# SH4-CONTROLS.net
KiCad netlist of a schematic drawn in Altium Designer
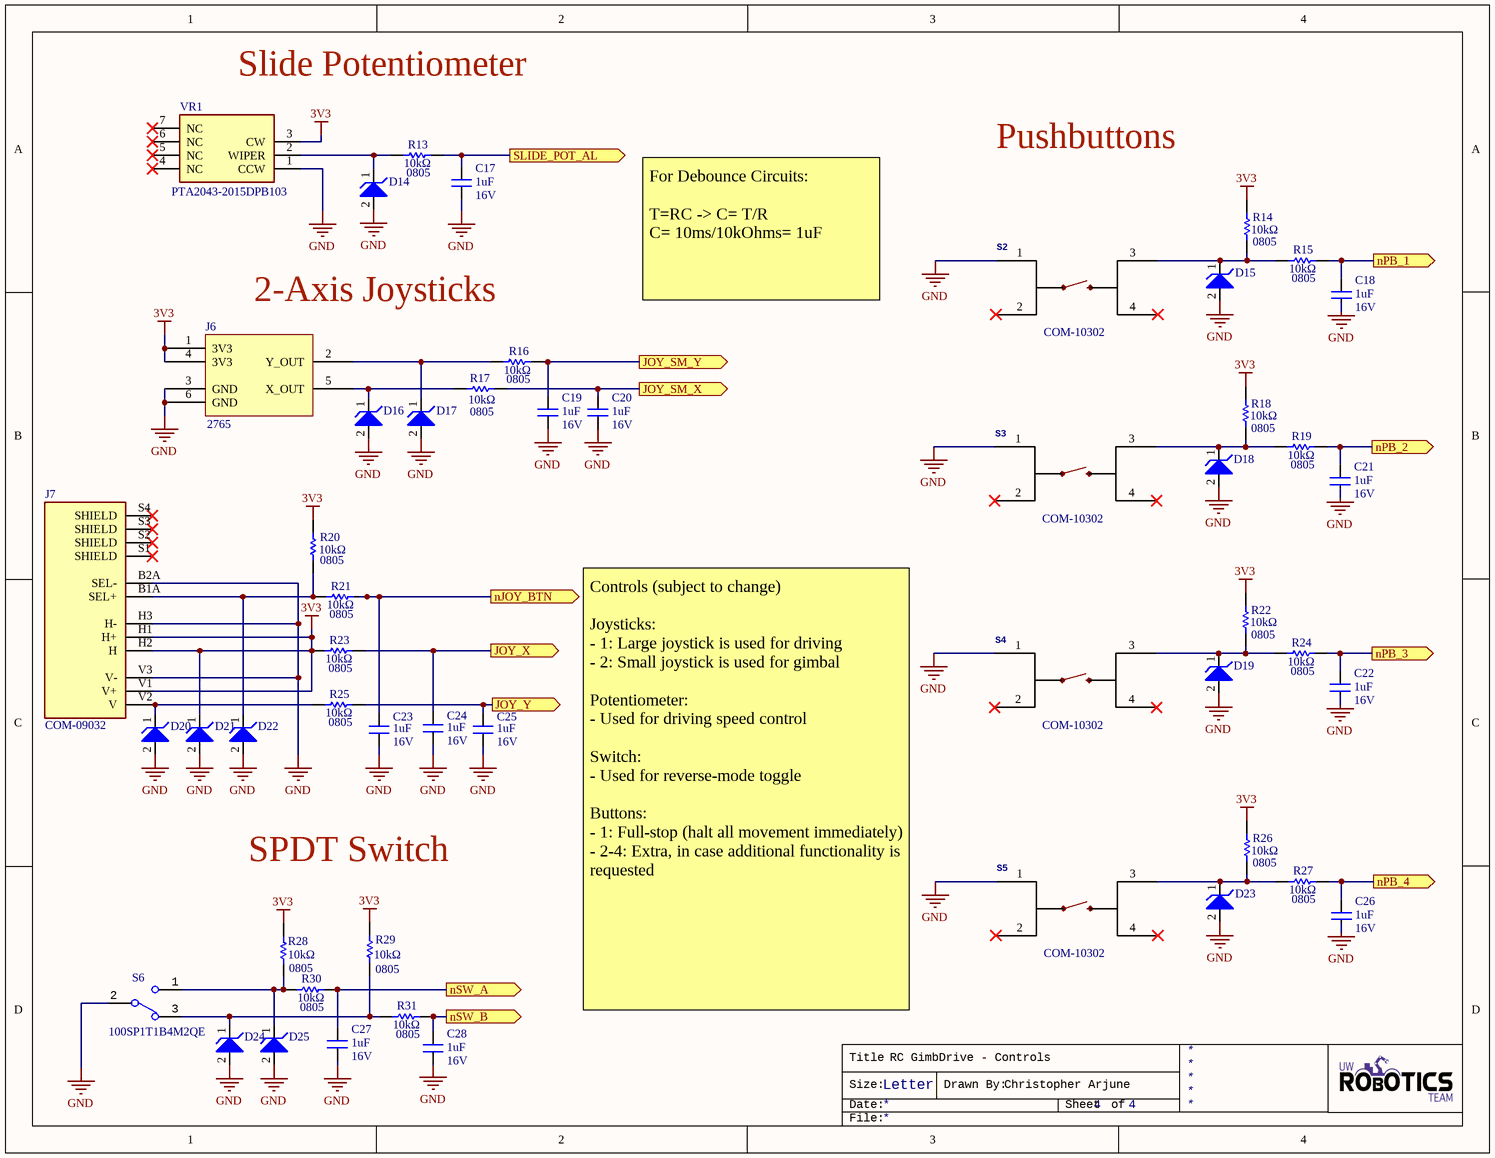
[diagram p0: SH4-CONTROLS.SchDoc]

(export (version "E")
  (design (tool "Eeschema 10.0.6"))
  (components
    (comp (ref "C17")
      (value "1uF")
      (footprint "CAPC2012X140N")
      (description "CAP CER 1UF 16V X7R 0805")
      (fields
        (field (name "TOLERANCE") "10%")
        (field (name "VOLTAGE RATING") "16V")
        (field (name "Comment") "CAP_1uF_16V_0805")
      )
      (libsource (lib "UWRT_Schematic_Library_2020") (part "CAP_1uF_16V_0805"))
    )
    (comp (ref "C18")
      (value "1uF")
      (footprint "CAPC2012X140N")
      (description "CAP CER 1UF 16V X7R 0805")
      (fields
        (field (name "TOLERANCE") "10%")
        (field (name "VOLTAGE RATING") "16V")
        (field (name "Comment") "CAP_1uF_16V_0805")
      )
      (libsource (lib "UWRT_Schematic_Library_2020") (part "CAP_1uF_16V_0805"))
    )
    (comp (ref "C19")
      (value "1uF")
      (footprint "CAPC2012X140N")
      (description "CAP CER 1UF 16V X7R 0805")
      (fields
        (field (name "TOLERANCE") "10%")
        (field (name "VOLTAGE RATING") "16V")
        (field (name "Comment") "CAP_1uF_16V_0805")
      )
      (libsource (lib "UWRT_Schematic_Library_2020") (part "CAP_1uF_16V_0805"))
    )
    (comp (ref "C20")
      (value "1uF")
      (footprint "CAPC2012X140N")
      (description "CAP CER 1UF 16V X7R 0805")
      (fields
        (field (name "TOLERANCE") "10%")
        (field (name "VOLTAGE RATING") "16V")
        (field (name "Comment") "CAP_1uF_16V_0805")
      )
      (libsource (lib "UWRT_Schematic_Library_2020") (part "CAP_1uF_16V_0805"))
    )
    (comp (ref "C21")
      (value "1uF")
      (footprint "CAPC2012X140N")
      (description "CAP CER 1UF 16V X7R 0805")
      (fields
        (field (name "TOLERANCE") "10%")
        (field (name "VOLTAGE RATING") "16V")
        (field (name "Comment") "CAP_1uF_16V_0805")
      )
      (libsource (lib "UWRT_Schematic_Library_2020") (part "CAP_1uF_16V_0805"))
    )
    (comp (ref "C22")
      (value "1uF")
      (footprint "CAPC2012X140N")
      (description "CAP CER 1UF 16V X7R 0805")
      (fields
        (field (name "TOLERANCE") "10%")
        (field (name "VOLTAGE RATING") "16V")
        (field (name "Comment") "CAP_1uF_16V_0805")
      )
      (libsource (lib "UWRT_Schematic_Library_2020") (part "CAP_1uF_16V_0805"))
    )
    (comp (ref "C23")
      (value "1uF")
      (footprint "CAPC2012X140N")
      (description "CAP CER 1UF 16V X7R 0805")
      (fields
        (field (name "TOLERANCE") "10%")
        (field (name "VOLTAGE RATING") "16V")
        (field (name "Comment") "CAP_1uF_16V_0805")
      )
      (libsource (lib "UWRT_Schematic_Library_2020") (part "CAP_1uF_16V_0805"))
    )
    (comp (ref "C24")
      (value "1uF")
      (footprint "CAPC2012X140N")
      (description "CAP CER 1UF 16V X7R 0805")
      (fields
        (field (name "TOLERANCE") "10%")
        (field (name "VOLTAGE RATING") "16V")
        (field (name "Comment") "CAP_1uF_16V_0805")
      )
      (libsource (lib "UWRT_Schematic_Library_2020") (part "CAP_1uF_16V_0805"))
    )
    (comp (ref "C25")
      (value "1uF")
      (footprint "CAPC2012X140N")
      (description "CAP CER 1UF 16V X7R 0805")
      (fields
        (field (name "TOLERANCE") "10%")
        (field (name "VOLTAGE RATING") "16V")
        (field (name "Comment") "CAP_1uF_16V_0805")
      )
      (libsource (lib "UWRT_Schematic_Library_2020") (part "CAP_1uF_16V_0805"))
    )
    (comp (ref "C26")
      (value "1uF")
      (footprint "CAPC2012X140N")
      (description "CAP CER 1UF 16V X7R 0805")
      (fields
        (field (name "TOLERANCE") "10%")
        (field (name "VOLTAGE RATING") "16V")
        (field (name "Comment") "CAP_1uF_16V_0805")
      )
      (libsource (lib "UWRT_Schematic_Library_2020") (part "CAP_1uF_16V_0805"))
    )
    (comp (ref "C27")
      (value "1uF")
      (footprint "CAPC2012X140N")
      (description "CAP CER 1UF 16V X7R 0805")
      (fields
        (field (name "TOLERANCE") "10%")
        (field (name "VOLTAGE RATING") "16V")
        (field (name "Comment") "CAP_1uF_16V_0805")
      )
      (libsource (lib "UWRT_Schematic_Library_2020") (part "CAP_1uF_16V_0805"))
    )
    (comp (ref "C28")
      (value "1uF")
      (footprint "CAPC2012X140N")
      (description "CAP CER 1UF 16V X7R 0805")
      (fields
        (field (name "TOLERANCE") "10%")
        (field (name "VOLTAGE RATING") "16V")
        (field (name "Comment") "CAP_1uF_16V_0805")
      )
      (libsource (lib "UWRT_Schematic_Library_2020") (part "CAP_1uF_16V_0805"))
    )
    (comp (ref "D14")
      (value "TVS_DIODE_UNIDIR_3.3V")
      (footprint "SOD523")
      (description "TVS DIODE 3.3V 14.1V SOD523. Used to protect each connector input line going into the MCU.")
      (libsource (lib "UWRT_Schematic_Library_2020") (part "TVS_DIODE_UNIDIR_3.3V"))
    )
    (comp (ref "D15")
      (value "TVS_DIODE_UNIDIR_3.3V")
      (footprint "SOD523")
      (description "TVS DIODE 3.3V 14.1V SOD523. Used to protect each connector input line going into the MCU.")
      (libsource (lib "UWRT_Schematic_Library_2020") (part "TVS_DIODE_UNIDIR_3.3V"))
    )
    (comp (ref "D16")
      (value "TVS_DIODE_UNIDIR_3.3V")
      (footprint "SOD523")
      (description "TVS DIODE 3.3V 14.1V SOD523. Used to protect each connector input line going into the MCU.")
      (libsource (lib "UWRT_Schematic_Library_2020") (part "TVS_DIODE_UNIDIR_3.3V"))
    )
    (comp (ref "D17")
      (value "TVS_DIODE_UNIDIR_3.3V")
      (footprint "SOD523")
      (description "TVS DIODE 3.3V 14.1V SOD523. Used to protect each connector input line going into the MCU.")
      (libsource (lib "UWRT_Schematic_Library_2020") (part "TVS_DIODE_UNIDIR_3.3V"))
    )
    (comp (ref "D18")
      (value "TVS_DIODE_UNIDIR_3.3V")
      (footprint "SOD523")
      (description "TVS DIODE 3.3V 14.1V SOD523. Used to protect each connector input line going into the MCU.")
      (libsource (lib "UWRT_Schematic_Library_2020") (part "TVS_DIODE_UNIDIR_3.3V"))
    )
    (comp (ref "D19")
      (value "TVS_DIODE_UNIDIR_3.3V")
      (footprint "SOD523")
      (description "TVS DIODE 3.3V 14.1V SOD523. Used to protect each connector input line going into the MCU.")
      (libsource (lib "UWRT_Schematic_Library_2020") (part "TVS_DIODE_UNIDIR_3.3V"))
    )
    (comp (ref "D20")
      (value "TVS_DIODE_UNIDIR_3.3V")
      (footprint "SOD523")
      (description "TVS DIODE 3.3V 14.1V SOD523. Used to protect each connector input line going into the MCU.")
      (libsource (lib "UWRT_Schematic_Library_2020") (part "TVS_DIODE_UNIDIR_3.3V"))
    )
    (comp (ref "D21")
      (value "TVS_DIODE_UNIDIR_3.3V")
      (footprint "SOD523")
      (description "TVS DIODE 3.3V 14.1V SOD523. Used to protect each connector input line going into the MCU.")
      (libsource (lib "UWRT_Schematic_Library_2020") (part "TVS_DIODE_UNIDIR_3.3V"))
    )
    (comp (ref "D22")
      (value "TVS_DIODE_UNIDIR_3.3V")
      (footprint "SOD523")
      (description "TVS DIODE 3.3V 14.1V SOD523. Used to protect each connector input line going into the MCU.")
      (libsource (lib "UWRT_Schematic_Library_2020") (part "TVS_DIODE_UNIDIR_3.3V"))
    )
    (comp (ref "D23")
      (value "TVS_DIODE_UNIDIR_3.3V")
      (footprint "SOD523")
      (description "TVS DIODE 3.3V 14.1V SOD523. Used to protect each connector input line going into the MCU.")
      (libsource (lib "UWRT_Schematic_Library_2020") (part "TVS_DIODE_UNIDIR_3.3V"))
    )
    (comp (ref "D24")
      (value "TVS_DIODE_UNIDIR_3.3V")
      (footprint "SOD523")
      (description "TVS DIODE 3.3V 14.1V SOD523. Used to protect each connector input line going into the MCU.")
      (libsource (lib "UWRT_Schematic_Library_2020") (part "TVS_DIODE_UNIDIR_3.3V"))
    )
    (comp (ref "D25")
      (value "TVS_DIODE_UNIDIR_3.3V")
      (footprint "SOD523")
      (description "TVS DIODE 3.3V 14.1V SOD523. Used to protect each connector input line going into the MCU.")
      (libsource (lib "UWRT_Schematic_Library_2020") (part "TVS_DIODE_UNIDIR_3.3V"))
    )
    (comp (ref "J6")
      (value "2_AXIS_JOYSTICK_SMALL")
      (footprint "2_AXIS_JOY_SMALL")
      (description "JOYSTICK 10K OHM 2 AXIS TH")
      (fields (field (name "MANUFACTURER PART NUMBER 1") "2765"))
      (libsource (lib "UWRT_Schematic_Library_2020") (part "2_AXIS_JOYSTICK_SMALL"))
    )
    (comp (ref "J7")
      (value "2_AXIS_JOYSTICK")
      (footprint "2_AXIS_JOY")
      (description "JOYSTICK 10K OHM 2 AXIS TH")
      (fields (field (name "MANUFACTURER PART NUMBER 1") "COM-09032"))
      (libsource (lib "UWRT_Schematic_Library_2020") (part "2_AXIS_JOYSTICK"))
    )
    (comp (ref "R13")
      (value "10kΩ")
      (footprint "RESC2012X60N")
      (description "RES SMD 10K OHM 1% 1/8W 0805")
      (fields
        (field (name "CASE CODE (IMPERIAL)") "0805")
        (field (name "TOLERANCE") "1%")
        (field (name "Comment") "RES_10kΩ_0805")
      )
      (libsource (lib "UWRT_Schematic_Library_2020") (part "RES_10kΩ_0805"))
    )
    (comp (ref "R14")
      (value "10kΩ")
      (footprint "RESC2012X60N")
      (description "RES SMD 10K OHM 1% 1/8W 0805")
      (fields
        (field (name "TOLERANCE") "1%")
        (field (name "CASE CODE (IMPERIAL)") "0805")
        (field (name "Comment") "RES_10kΩ_0805")
      )
      (libsource (lib "UWRT_Schematic_Library_2020") (part "RES_10kΩ_0805"))
    )
    (comp (ref "R15")
      (value "10kΩ")
      (footprint "RESC2012X60N")
      (description "RES SMD 10K OHM 1% 1/8W 0805")
      (fields
        (field (name "CASE CODE (IMPERIAL)") "0805")
        (field (name "TOLERANCE") "1%")
        (field (name "Comment") "RES_10kΩ_0805")
      )
      (libsource (lib "UWRT_Schematic_Library_2020") (part "RES_10kΩ_0805"))
    )
    (comp (ref "R16")
      (value "10kΩ")
      (footprint "RESC2012X60N")
      (description "RES SMD 10K OHM 1% 1/8W 0805")
      (fields
        (field (name "CASE CODE (IMPERIAL)") "0805")
        (field (name "TOLERANCE") "1%")
        (field (name "Comment") "RES_10kΩ_0805")
      )
      (libsource (lib "UWRT_Schematic_Library_2020") (part "RES_10kΩ_0805"))
    )
    (comp (ref "R17")
      (value "10kΩ")
      (footprint "RESC2012X60N")
      (description "RES SMD 10K OHM 1% 1/8W 0805")
      (fields
        (field (name "CASE CODE (IMPERIAL)") "0805")
        (field (name "TOLERANCE") "1%")
        (field (name "Comment") "RES_10kΩ_0805")
      )
      (libsource (lib "UWRT_Schematic_Library_2020") (part "RES_10kΩ_0805"))
    )
    (comp (ref "R18")
      (value "10kΩ")
      (footprint "RESC2012X60N")
      (description "RES SMD 10K OHM 1% 1/8W 0805")
      (fields
        (field (name "TOLERANCE") "1%")
        (field (name "CASE CODE (IMPERIAL)") "0805")
        (field (name "Comment") "RES_10kΩ_0805")
      )
      (libsource (lib "UWRT_Schematic_Library_2020") (part "RES_10kΩ_0805"))
    )
    (comp (ref "R19")
      (value "10kΩ")
      (footprint "RESC2012X60N")
      (description "RES SMD 10K OHM 1% 1/8W 0805")
      (fields
        (field (name "CASE CODE (IMPERIAL)") "0805")
        (field (name "TOLERANCE") "1%")
        (field (name "Comment") "RES_10kΩ_0805")
      )
      (libsource (lib "UWRT_Schematic_Library_2020") (part "RES_10kΩ_0805"))
    )
    (comp (ref "R20")
      (value "10kΩ")
      (footprint "RESC2012X60N")
      (description "RES SMD 10K OHM 1% 1/8W 0805")
      (fields
        (field (name "TOLERANCE") "1%")
        (field (name "CASE CODE (IMPERIAL)") "0805")
        (field (name "Comment") "RES_10kΩ_0805")
      )
      (libsource (lib "UWRT_Schematic_Library_2020") (part "RES_10kΩ_0805"))
    )
    (comp (ref "R21")
      (value "10kΩ")
      (footprint "RESC2012X60N")
      (description "RES SMD 10K OHM 1% 1/8W 0805")
      (fields
        (field (name "CASE CODE (IMPERIAL)") "0805")
        (field (name "TOLERANCE") "1%")
        (field (name "Comment") "RES_10kΩ_0805")
      )
      (libsource (lib "UWRT_Schematic_Library_2020") (part "RES_10kΩ_0805"))
    )
    (comp (ref "R22")
      (value "10kΩ")
      (footprint "RESC2012X60N")
      (description "RES SMD 10K OHM 1% 1/8W 0805")
      (fields
        (field (name "TOLERANCE") "1%")
        (field (name "CASE CODE (IMPERIAL)") "0805")
        (field (name "Comment") "RES_10kΩ_0805")
      )
      (libsource (lib "UWRT_Schematic_Library_2020") (part "RES_10kΩ_0805"))
    )
    (comp (ref "R23")
      (value "10kΩ")
      (footprint "RESC2012X60N")
      (description "RES SMD 10K OHM 1% 1/8W 0805")
      (fields
        (field (name "CASE CODE (IMPERIAL)") "0805")
        (field (name "TOLERANCE") "1%")
        (field (name "Comment") "RES_10kΩ_0805")
      )
      (libsource (lib "UWRT_Schematic_Library_2020") (part "RES_10kΩ_0805"))
    )
    (comp (ref "R24")
      (value "10kΩ")
      (footprint "RESC2012X60N")
      (description "RES SMD 10K OHM 1% 1/8W 0805")
      (fields
        (field (name "CASE CODE (IMPERIAL)") "0805")
        (field (name "TOLERANCE") "1%")
        (field (name "Comment") "RES_10kΩ_0805")
      )
      (libsource (lib "UWRT_Schematic_Library_2020") (part "RES_10kΩ_0805"))
    )
    (comp (ref "R25")
      (value "10kΩ")
      (footprint "RESC2012X60N")
      (description "RES SMD 10K OHM 1% 1/8W 0805")
      (fields
        (field (name "CASE CODE (IMPERIAL)") "0805")
        (field (name "TOLERANCE") "1%")
        (field (name "Comment") "RES_10kΩ_0805")
      )
      (libsource (lib "UWRT_Schematic_Library_2020") (part "RES_10kΩ_0805"))
    )
    (comp (ref "R26")
      (value "10kΩ")
      (footprint "RESC2012X60N")
      (description "RES SMD 10K OHM 1% 1/8W 0805")
      (fields
        (field (name "TOLERANCE") "1%")
        (field (name "CASE CODE (IMPERIAL)") "0805")
        (field (name "Comment") "RES_10kΩ_0805")
      )
      (libsource (lib "UWRT_Schematic_Library_2020") (part "RES_10kΩ_0805"))
    )
    (comp (ref "R27")
      (value "10kΩ")
      (footprint "RESC2012X60N")
      (description "RES SMD 10K OHM 1% 1/8W 0805")
      (fields
        (field (name "CASE CODE (IMPERIAL)") "0805")
        (field (name "TOLERANCE") "1%")
        (field (name "Comment") "RES_10kΩ_0805")
      )
      (libsource (lib "UWRT_Schematic_Library_2020") (part "RES_10kΩ_0805"))
    )
    (comp (ref "R28")
      (value "10kΩ")
      (footprint "RESC2012X60N")
      (description "RES SMD 10K OHM 1% 1/8W 0805")
      (fields
        (field (name "TOLERANCE") "1%")
        (field (name "CASE CODE (IMPERIAL)") "0805")
        (field (name "Comment") "RES_10kΩ_0805")
      )
      (libsource (lib "UWRT_Schematic_Library_2020") (part "RES_10kΩ_0805"))
    )
    (comp (ref "R29")
      (value "10kΩ")
      (footprint "RESC2012X60N")
      (description "RES SMD 10K OHM 1% 1/8W 0805")
      (fields
        (field (name "TOLERANCE") "1%")
        (field (name "CASE CODE (IMPERIAL)") "0805")
        (field (name "Comment") "RES_10kΩ_0805")
      )
      (libsource (lib "UWRT_Schematic_Library_2020") (part "RES_10kΩ_0805"))
    )
    (comp (ref "R30")
      (value "10kΩ")
      (footprint "RESC2012X60N")
      (description "RES SMD 10K OHM 1% 1/8W 0805")
      (fields
        (field (name "CASE CODE (IMPERIAL)") "0805")
        (field (name "TOLERANCE") "1%")
        (field (name "Comment") "RES_10kΩ_0805")
      )
      (libsource (lib "UWRT_Schematic_Library_2020") (part "RES_10kΩ_0805"))
    )
    (comp (ref "R31")
      (value "10kΩ")
      (footprint "RESC2012X60N")
      (description "RES SMD 10K OHM 1% 1/8W 0805")
      (fields
        (field (name "CASE CODE (IMPERIAL)") "0805")
        (field (name "TOLERANCE") "1%")
        (field (name "Comment") "RES_10kΩ_0805")
      )
      (libsource (lib "UWRT_Schematic_Library_2020") (part "RES_10kΩ_0805"))
    )
    (comp (ref "S2")
      (value "Pushbutton")
      (footprint "TACTILE_SWITCH_PTH_12MM")
      (description "Momentary Switch (Pushbutton) - SPST")
      (fields (field (name "MANUFACTURER PART NUMBER 1") "COM-10302"))
      (libsource (lib "UWRT_Schematic_Library_2020") (part "MOMENTARY_SWITCH_TH"))
    )
    (comp (ref "S3")
      (value "Pushbutton")
      (footprint "TACTILE_SWITCH_PTH_12MM")
      (description "Momentary Switch (Pushbutton) - SPST")
      (fields (field (name "MANUFACTURER PART NUMBER 1") "COM-10302"))
      (libsource (lib "UWRT_Schematic_Library_2020") (part "MOMENTARY_SWITCH_TH"))
    )
    (comp (ref "S4")
      (value "Pushbutton")
      (footprint "TACTILE_SWITCH_PTH_12MM")
      (description "Momentary Switch (Pushbutton) - SPST")
      (fields (field (name "MANUFACTURER PART NUMBER 1") "COM-10302"))
      (libsource (lib "UWRT_Schematic_Library_2020") (part "MOMENTARY_SWITCH_TH"))
    )
    (comp (ref "S5")
      (value "Pushbutton")
      (footprint "TACTILE_SWITCH_PTH_12MM")
      (description "Momentary Switch (Pushbutton) - SPST")
      (fields (field (name "MANUFACTURER PART NUMBER 1") "COM-10302"))
      (libsource (lib "UWRT_Schematic_Library_2020") (part "MOMENTARY_SWITCH_TH"))
    )
    (comp (ref "S6")
      (value "SW_SPDT")
      (footprint "100SP1T1B4M2QE")
      (description "SWITCH TOGGLE SPDT 5A 120V")
      (fields (field (name "MANUFACTURER PART NUMBER 1") "100SP1T1B4M2QE"))
      (libsource (lib "UWRT_Schematic_Library_2020") (part "SW_SPDT"))
    )
    (comp (ref "VR1")
      (value "POT_10K_SLIDE")
      (footprint "PTA20432015CPB103")
      (description "SLIDE POT 10K OHM 0.1W TOP 20MM")
      (fields
        (field (name "MANUFACTURER PART NUMBER 1") "PTA2043-2015DPB103")
        (field (name "TOLERANCE") "20%")
      )
      (libsource (lib "UWRT_Schematic_Library_2020") (part "POT_10K_SLIDE"))
    )
  )
  (nets
    (net (code "1") (name "/JOY_SM_X") (class "Default")
      (node (ref "C20") (pin "2") (pinfunction "2_2") (pintype "passive"))
      (node (ref "R17") (pin "2") (pinfunction "2_2") (pintype "passive"))
    )
    (net (code "2") (name "/JOY_SM_Y") (class "Default")
      (node (ref "C19") (pin "2") (pinfunction "2_2") (pintype "passive"))
      (node (ref "R16") (pin "2") (pinfunction "2_2") (pintype "passive"))
    )
    (net (code "3") (name "/JOY_X") (class "Default")
      (node (ref "C24") (pin "2") (pinfunction "2_2") (pintype "passive"))
      (node (ref "R23") (pin "2") (pinfunction "2_2") (pintype "passive"))
    )
    (net (code "4") (name "/JOY_Y") (class "Default")
      (node (ref "C25") (pin "2") (pinfunction "2_2") (pintype "passive"))
      (node (ref "R25") (pin "2") (pinfunction "2_2") (pintype "passive"))
    )
    (net (code "5") (name "/SLIDE_POT_AL") (class "Default")
      (node (ref "C17") (pin "2") (pinfunction "2_2") (pintype "passive"))
      (node (ref "R13") (pin "2") (pinfunction "2_2") (pintype "passive"))
    )
    (net (code "6") (name "/nJOY_BTN") (class "Default")
      (node (ref "C23") (pin "2") (pinfunction "2_2") (pintype "passive"))
      (node (ref "R21") (pin "2") (pinfunction "2_2") (pintype "passive"))
    )
    (net (code "7") (name "/nPB_1") (class "Default")
      (node (ref "C18") (pin "2") (pinfunction "2_2") (pintype "passive"))
      (node (ref "R15") (pin "2") (pinfunction "2_2") (pintype "passive"))
    )
    (net (code "8") (name "/nPB_2") (class "Default")
      (node (ref "C21") (pin "2") (pinfunction "2_2") (pintype "passive"))
      (node (ref "R19") (pin "2") (pinfunction "2_2") (pintype "passive"))
    )
    (net (code "9") (name "/nPB_3") (class "Default")
      (node (ref "C22") (pin "2") (pinfunction "2_2") (pintype "passive"))
      (node (ref "R24") (pin "2") (pinfunction "2_2") (pintype "passive"))
    )
    (net (code "10") (name "/nPB_4") (class "Default")
      (node (ref "C26") (pin "2") (pinfunction "2_2") (pintype "passive"))
      (node (ref "R27") (pin "2") (pinfunction "2_2") (pintype "passive"))
    )
    (net (code "11") (name "/nSW_A") (class "Default")
      (node (ref "C27") (pin "2") (pinfunction "2_2") (pintype "passive"))
      (node (ref "R30") (pin "2") (pinfunction "2_2") (pintype "passive"))
    )
    (net (code "12") (name "/nSW_B") (class "Default")
      (node (ref "C28") (pin "2") (pinfunction "2_2") (pintype "passive"))
      (node (ref "R31") (pin "2") (pinfunction "2_2") (pintype "passive"))
    )
    (net (code "13") (name "3V3") (class "Default")
      (node (ref "D21") (pin "1") (pinfunction "1_1") (pintype "passive"))
      (node (ref "J6") (pin "1") (pinfunction "3V3_1") (pintype "passive"))
      (node (ref "J6") (pin "4") (pinfunction "3V3_4") (pintype "passive"))
      (node (ref "J7") (pin "H1") (pinfunction "H+_H1") (pintype "passive"))
      (node (ref "J7") (pin "H2") (pinfunction "H_H2") (pintype "passive"))
      (node (ref "J7") (pin "V1") (pinfunction "V+_V1") (pintype "passive"))
      (node (ref "R14") (pin "1") (pinfunction "1_1") (pintype "passive"))
      (node (ref "R18") (pin "1") (pinfunction "1_1") (pintype "passive"))
      (node (ref "R20") (pin "1") (pinfunction "1_1") (pintype "passive"))
      (node (ref "R22") (pin "1") (pinfunction "1_1") (pintype "passive"))
      (node (ref "R23") (pin "1") (pinfunction "1_1") (pintype "passive"))
      (node (ref "R26") (pin "1") (pinfunction "1_1") (pintype "passive"))
      (node (ref "R28") (pin "1") (pinfunction "1_1") (pintype "passive"))
      (node (ref "R29") (pin "1") (pinfunction "1_1") (pintype "passive"))
      (node (ref "VR1") (pin "3") (pinfunction "CW_3") (pintype "passive"))
    )
    (net (code "14") (name "GND") (class "Default")
      (node (ref "C17") (pin "1") (pinfunction "1_1") (pintype "passive"))
      (node (ref "C18") (pin "1") (pinfunction "1_1") (pintype "passive"))
      (node (ref "C19") (pin "1") (pinfunction "1_1") (pintype "passive"))
      (node (ref "C20") (pin "1") (pinfunction "1_1") (pintype "passive"))
      (node (ref "C21") (pin "1") (pinfunction "1_1") (pintype "passive"))
      (node (ref "C22") (pin "1") (pinfunction "1_1") (pintype "passive"))
      (node (ref "C23") (pin "1") (pinfunction "1_1") (pintype "passive"))
      (node (ref "C24") (pin "1") (pinfunction "1_1") (pintype "passive"))
      (node (ref "C25") (pin "1") (pinfunction "1_1") (pintype "passive"))
      (node (ref "C26") (pin "1") (pinfunction "1_1") (pintype "passive"))
      (node (ref "C27") (pin "1") (pinfunction "1_1") (pintype "passive"))
      (node (ref "C28") (pin "1") (pinfunction "1_1") (pintype "passive"))
      (node (ref "D14") (pin "2") (pinfunction "2_2") (pintype "passive"))
      (node (ref "D15") (pin "2") (pinfunction "2_2") (pintype "passive"))
      (node (ref "D16") (pin "2") (pinfunction "2_2") (pintype "passive"))
      (node (ref "D17") (pin "2") (pinfunction "2_2") (pintype "passive"))
      (node (ref "D18") (pin "2") (pinfunction "2_2") (pintype "passive"))
      (node (ref "D19") (pin "2") (pinfunction "2_2") (pintype "passive"))
      (node (ref "D20") (pin "2") (pinfunction "2_2") (pintype "passive"))
      (node (ref "D21") (pin "2") (pinfunction "2_2") (pintype "passive"))
      (node (ref "D22") (pin "2") (pinfunction "2_2") (pintype "passive"))
      (node (ref "D23") (pin "2") (pinfunction "2_2") (pintype "passive"))
      (node (ref "D24") (pin "2") (pinfunction "2_2") (pintype "passive"))
      (node (ref "D25") (pin "2") (pinfunction "2_2") (pintype "passive"))
      (node (ref "J6") (pin "3") (pinfunction "GND_3") (pintype "passive"))
      (node (ref "J6") (pin "6") (pinfunction "GND_6") (pintype "passive"))
      (node (ref "J7") (pin "B2A") (pinfunction "SEL-_B2A") (pintype "passive"))
      (node (ref "J7") (pin "H3") (pinfunction "H-_H3") (pintype "passive"))
      (node (ref "J7") (pin "V3") (pinfunction "V-_V3") (pintype "passive"))
      (node (ref "S2") (pin "1") (pinfunction "1_1") (pintype "passive"))
      (node (ref "S3") (pin "1") (pinfunction "1_1") (pintype "passive"))
      (node (ref "S4") (pin "1") (pinfunction "1_1") (pintype "passive"))
      (node (ref "S5") (pin "1") (pinfunction "1_1") (pintype "passive"))
      (node (ref "S6") (pin "2") (pinfunction "2_2") (pintype "passive"))
      (node (ref "VR1") (pin "1") (pinfunction "CCW_1") (pintype "passive"))
    )
    (net (code "15") (name "Net-(D15-Pad1)") (class "Default")
      (node (ref "D15") (pin "1") (pinfunction "1_1") (pintype "passive"))
      (node (ref "R14") (pin "2") (pinfunction "2_2") (pintype "passive"))
      (node (ref "R15") (pin "1") (pinfunction "1_1") (pintype "passive"))
      (node (ref "S2") (pin "3") (pinfunction "3_3") (pintype "passive"))
    )
    (net (code "16") (name "Net-(D18-Pad1)") (class "Default")
      (node (ref "D18") (pin "1") (pinfunction "1_1") (pintype "passive"))
      (node (ref "R18") (pin "2") (pinfunction "2_2") (pintype "passive"))
      (node (ref "R19") (pin "1") (pinfunction "1_1") (pintype "passive"))
      (node (ref "S3") (pin "3") (pinfunction "3_3") (pintype "passive"))
    )
    (net (code "17") (name "Net-(D19-Pad1)") (class "Default")
      (node (ref "D19") (pin "1") (pinfunction "1_1") (pintype "passive"))
      (node (ref "R22") (pin "2") (pinfunction "2_2") (pintype "passive"))
      (node (ref "R24") (pin "1") (pinfunction "1_1") (pintype "passive"))
      (node (ref "S4") (pin "3") (pinfunction "3_3") (pintype "passive"))
    )
    (net (code "18") (name "Net-(D23-Pad1)") (class "Default")
      (node (ref "D23") (pin "1") (pinfunction "1_1") (pintype "passive"))
      (node (ref "R26") (pin "2") (pinfunction "2_2") (pintype "passive"))
      (node (ref "R27") (pin "1") (pinfunction "1_1") (pintype "passive"))
      (node (ref "S5") (pin "3") (pinfunction "3_3") (pintype "passive"))
    )
    (net (code "19") (name "Net-(D24-Pad1)") (class "Default")
      (node (ref "D24") (pin "1") (pinfunction "1_1") (pintype "passive"))
      (node (ref "R29") (pin "2") (pinfunction "2_2") (pintype "passive"))
      (node (ref "R31") (pin "1") (pinfunction "1_1") (pintype "passive"))
      (node (ref "S6") (pin "3") (pinfunction "3_3") (pintype "passive"))
    )
    (net (code "20") (name "Net-(D25-Pad1)") (class "Default")
      (node (ref "D25") (pin "1") (pinfunction "1_1") (pintype "passive"))
      (node (ref "R28") (pin "2") (pinfunction "2_2") (pintype "passive"))
      (node (ref "R30") (pin "1") (pinfunction "1_1") (pintype "passive"))
      (node (ref "S6") (pin "1") (pinfunction "1_1") (pintype "passive"))
    )
    (net (code "21") (name "Net-(J6-X_OUT)") (class "Default")
      (node (ref "D16") (pin "1") (pinfunction "1_1") (pintype "passive"))
      (node (ref "J6") (pin "5") (pinfunction "X_OUT_5") (pintype "passive"))
      (node (ref "R17") (pin "1") (pinfunction "1_1") (pintype "passive"))
    )
    (net (code "22") (name "Net-(J6-Y_OUT)") (class "Default")
      (node (ref "D17") (pin "1") (pinfunction "1_1") (pintype "passive"))
      (node (ref "J6") (pin "2") (pinfunction "Y_OUT_2") (pintype "passive"))
      (node (ref "R16") (pin "1") (pinfunction "1_1") (pintype "passive"))
    )
    (net (code "23") (name "Net-(J7-SEL+)") (class "Default")
      (node (ref "D22") (pin "1") (pinfunction "1_1") (pintype "passive"))
      (node (ref "J7") (pin "B1A") (pinfunction "SEL+_B1A") (pintype "passive"))
      (node (ref "R20") (pin "2") (pinfunction "2_2") (pintype "passive"))
      (node (ref "R21") (pin "1") (pinfunction "1_1") (pintype "passive"))
    )
    (net (code "24") (name "Net-(J7-V)") (class "Default")
      (node (ref "D20") (pin "1") (pinfunction "1_1") (pintype "passive"))
      (node (ref "J7") (pin "V2") (pinfunction "V_V2") (pintype "passive"))
      (node (ref "R25") (pin "1") (pinfunction "1_1") (pintype "passive"))
    )
    (net (code "25") (name "Net-(VR1-WIPER)") (class "Default")
      (node (ref "D14") (pin "1") (pinfunction "1_1") (pintype "passive"))
      (node (ref "R13") (pin "1") (pinfunction "1_1") (pintype "passive"))
      (node (ref "VR1") (pin "2") (pinfunction "WIPER_2") (pintype "passive"))
    )
    (net (code "26") (name "unconnected-(J7-SHIELD-PadS1)") (class "Default")
      (node (ref "J7") (pin "S1") (pinfunction "SHIELD_S1") (pintype "passive+no_connect"))
    )
    (net (code "27") (name "unconnected-(J7-SHIELD-PadS2)") (class "Default")
      (node (ref "J7") (pin "S2") (pinfunction "SHIELD_S2") (pintype "passive+no_connect"))
    )
    (net (code "28") (name "unconnected-(J7-SHIELD-PadS3)") (class "Default")
      (node (ref "J7") (pin "S3") (pinfunction "SHIELD_S3") (pintype "passive+no_connect"))
    )
    (net (code "29") (name "unconnected-(J7-SHIELD-PadS4)") (class "Default")
      (node (ref "J7") (pin "S4") (pinfunction "SHIELD_S4") (pintype "passive+no_connect"))
    )
    (net (code "30") (name "unconnected-(S2-Pad2)") (class "Default")
      (node (ref "S2") (pin "2") (pinfunction "2_2") (pintype "passive+no_connect"))
    )
    (net (code "31") (name "unconnected-(S2-Pad4)") (class "Default")
      (node (ref "S2") (pin "4") (pinfunction "4_4") (pintype "passive+no_connect"))
    )
    (net (code "32") (name "unconnected-(S3-Pad2)") (class "Default")
      (node (ref "S3") (pin "2") (pinfunction "2_2") (pintype "passive+no_connect"))
    )
    (net (code "33") (name "unconnected-(S3-Pad4)") (class "Default")
      (node (ref "S3") (pin "4") (pinfunction "4_4") (pintype "passive+no_connect"))
    )
    (net (code "34") (name "unconnected-(S4-Pad2)") (class "Default")
      (node (ref "S4") (pin "2") (pinfunction "2_2") (pintype "passive+no_connect"))
    )
    (net (code "35") (name "unconnected-(S4-Pad4)") (class "Default")
      (node (ref "S4") (pin "4") (pinfunction "4_4") (pintype "passive+no_connect"))
    )
    (net (code "36") (name "unconnected-(S5-Pad2)") (class "Default")
      (node (ref "S5") (pin "2") (pinfunction "2_2") (pintype "passive+no_connect"))
    )
    (net (code "37") (name "unconnected-(S5-Pad4)") (class "Default")
      (node (ref "S5") (pin "4") (pinfunction "4_4") (pintype "passive+no_connect"))
    )
    (net (code "38") (name "unconnected-(VR1-NC-Pad4)") (class "Default")
      (node (ref "VR1") (pin "4") (pinfunction "NC_4") (pintype "passive+no_connect"))
    )
    (net (code "39") (name "unconnected-(VR1-NC-Pad5)") (class "Default")
      (node (ref "VR1") (pin "5") (pinfunction "NC_5") (pintype "passive+no_connect"))
    )
    (net (code "40") (name "unconnected-(VR1-NC-Pad6)") (class "Default")
      (node (ref "VR1") (pin "6") (pinfunction "NC_6") (pintype "passive+no_connect"))
    )
    (net (code "41") (name "unconnected-(VR1-NC-Pad7)") (class "Default")
      (node (ref "VR1") (pin "7") (pinfunction "NC_7") (pintype "passive+no_connect"))
    )
  )
)
